# BoardA-FPGA2.net
KiCad netlist of a schematic drawn in Altium Designer
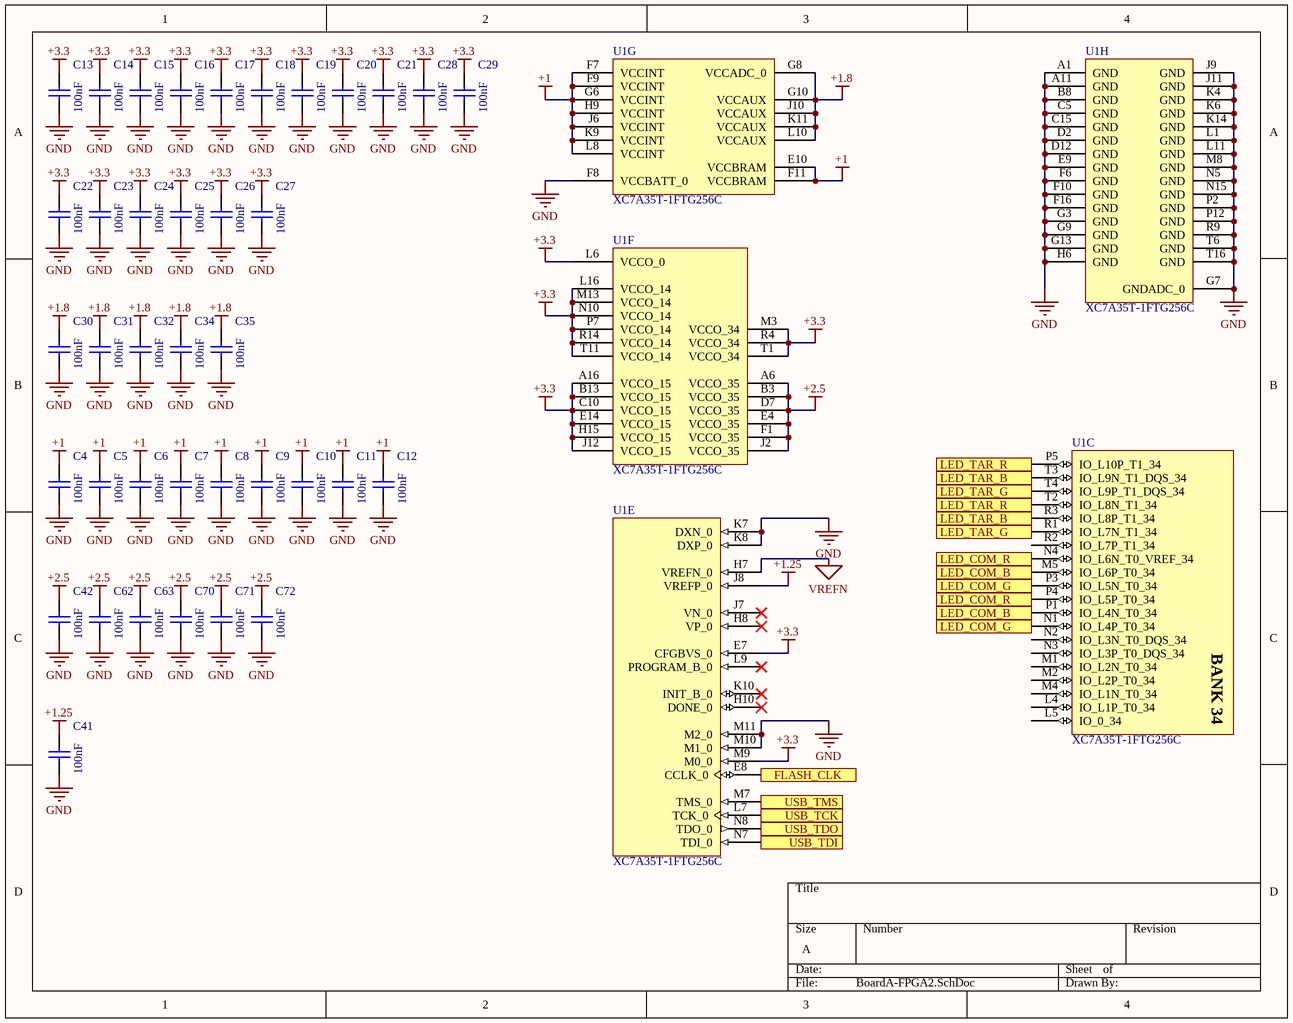
[diagram p0: BoardA-FPGA2.SchDoc]

(export (version "E")
  (design (tool "Eeschema 10.0.6"))
  (components
    (comp (ref "C4")
      (value "100nF")
      (footprint "CAPC0603X33X15ML03T05")
      (fields (field (name "MANUFACTURER") "Samsung") (field (name "PART NUMBER") "CL03A104KQ3NNNC"))
      (libsource (lib "Altium Content Vault") (part "CAP"))
    )
    (comp (ref "C5")
      (value "100nF")
      (footprint "CAPC0603X33X15ML03T05")
      (fields (field (name "MANUFACTURER") "Samsung") (field (name "PART NUMBER") "CL03A104KQ3NNNC"))
      (libsource (lib "Altium Content Vault") (part "CAP"))
    )
    (comp (ref "C6")
      (value "100nF")
      (footprint "CAPC0603X33X15ML03T05")
      (fields (field (name "MANUFACTURER") "Samsung") (field (name "PART NUMBER") "CL03A104KQ3NNNC"))
      (libsource (lib "Altium Content Vault") (part "CAP"))
    )
    (comp (ref "C7")
      (value "100nF")
      (footprint "CAPC0603X33X15ML03T05")
      (fields (field (name "MANUFACTURER") "Samsung") (field (name "PART NUMBER") "CL03A104KQ3NNNC"))
      (libsource (lib "Altium Content Vault") (part "CAP"))
    )
    (comp (ref "C8")
      (value "100nF")
      (footprint "CAPC0603X33X15ML03T05")
      (fields (field (name "MANUFACTURER") "Samsung") (field (name "PART NUMBER") "CL03A104KQ3NNNC"))
      (libsource (lib "Altium Content Vault") (part "CAP"))
    )
    (comp (ref "C9")
      (value "100nF")
      (footprint "CAPC0603X33X15ML03T05")
      (fields (field (name "MANUFACTURER") "Samsung") (field (name "PART NUMBER") "CL03A104KQ3NNNC"))
      (libsource (lib "Altium Content Vault") (part "CAP"))
    )
    (comp (ref "C10")
      (value "100nF")
      (footprint "CAPC0603X33X15ML03T05")
      (fields (field (name "MANUFACTURER") "Samsung") (field (name "PART NUMBER") "CL03A104KQ3NNNC"))
      (libsource (lib "Altium Content Vault") (part "CAP"))
    )
    (comp (ref "C11")
      (value "100nF")
      (footprint "CAPC0603X33X15ML03T05")
      (fields (field (name "MANUFACTURER") "Samsung") (field (name "PART NUMBER") "CL03A104KQ3NNNC"))
      (libsource (lib "Altium Content Vault") (part "CAP"))
    )
    (comp (ref "C12")
      (value "100nF")
      (footprint "CAPC0603X33X15ML03T05")
      (fields (field (name "MANUFACTURER") "Samsung") (field (name "PART NUMBER") "CL03A104KQ3NNNC"))
      (libsource (lib "Altium Content Vault") (part "CAP"))
    )
    (comp (ref "C13")
      (value "100nF")
      (footprint "CAPC0603X33X15ML03T05")
      (fields (field (name "MANUFACTURER") "Samsung") (field (name "PART NUMBER") "CL03A104KQ3NNNC"))
      (libsource (lib "Altium Content Vault") (part "CAP"))
    )
    (comp (ref "C14")
      (value "100nF")
      (footprint "CAPC0603X33X15ML03T05")
      (fields (field (name "MANUFACTURER") "Samsung") (field (name "PART NUMBER") "CL03A104KQ3NNNC"))
      (libsource (lib "Altium Content Vault") (part "CAP"))
    )
    (comp (ref "C15")
      (value "100nF")
      (footprint "CAPC0603X33X15ML03T05")
      (fields (field (name "MANUFACTURER") "Samsung") (field (name "PART NUMBER") "CL03A104KQ3NNNC"))
      (libsource (lib "Altium Content Vault") (part "CAP"))
    )
    (comp (ref "C16")
      (value "100nF")
      (footprint "CAPC0603X33X15ML03T05")
      (fields (field (name "MANUFACTURER") "Samsung") (field (name "PART NUMBER") "CL03A104KQ3NNNC"))
      (libsource (lib "Altium Content Vault") (part "CAP"))
    )
    (comp (ref "C17")
      (value "100nF")
      (footprint "CAPC0603X33X15ML03T05")
      (fields (field (name "MANUFACTURER") "Samsung") (field (name "PART NUMBER") "CL03A104KQ3NNNC"))
      (libsource (lib "Altium Content Vault") (part "CAP"))
    )
    (comp (ref "C18")
      (value "100nF")
      (footprint "CAPC0603X33X15ML03T05")
      (fields (field (name "MANUFACTURER") "Samsung") (field (name "PART NUMBER") "CL03A104KQ3NNNC"))
      (libsource (lib "Altium Content Vault") (part "CAP"))
    )
    (comp (ref "C19")
      (value "100nF")
      (footprint "CAPC0603X33X15ML03T05")
      (fields (field (name "MANUFACTURER") "Samsung") (field (name "PART NUMBER") "CL03A104KQ3NNNC"))
      (libsource (lib "Altium Content Vault") (part "CAP"))
    )
    (comp (ref "C20")
      (value "100nF")
      (footprint "CAPC0603X33X15ML03T05")
      (fields (field (name "MANUFACTURER") "Samsung") (field (name "PART NUMBER") "CL03A104KQ3NNNC"))
      (libsource (lib "Altium Content Vault") (part "CAP"))
    )
    (comp (ref "C21")
      (value "100nF")
      (footprint "CAPC0603X33X15ML03T05")
      (fields (field (name "MANUFACTURER") "Samsung") (field (name "PART NUMBER") "CL03A104KQ3NNNC"))
      (libsource (lib "Altium Content Vault") (part "CAP"))
    )
    (comp (ref "C22")
      (value "100nF")
      (footprint "CAPC0603X33X15ML03T05")
      (fields (field (name "MANUFACTURER") "Samsung") (field (name "PART NUMBER") "CL03A104KQ3NNNC"))
      (libsource (lib "Altium Content Vault") (part "CAP"))
    )
    (comp (ref "C23")
      (value "100nF")
      (footprint "CAPC0603X33X15ML03T05")
      (fields (field (name "MANUFACTURER") "Samsung") (field (name "PART NUMBER") "CL03A104KQ3NNNC"))
      (libsource (lib "Altium Content Vault") (part "CAP"))
    )
    (comp (ref "C24")
      (value "100nF")
      (footprint "CAPC0603X33X15ML03T05")
      (fields (field (name "MANUFACTURER") "Samsung") (field (name "PART NUMBER") "CL03A104KQ3NNNC"))
      (libsource (lib "Altium Content Vault") (part "CAP"))
    )
    (comp (ref "C25")
      (value "100nF")
      (footprint "CAPC0603X33X15ML03T05")
      (fields (field (name "MANUFACTURER") "Samsung") (field (name "PART NUMBER") "CL03A104KQ3NNNC"))
      (libsource (lib "Altium Content Vault") (part "CAP"))
    )
    (comp (ref "C26")
      (value "100nF")
      (footprint "CAPC0603X33X15ML03T05")
      (fields (field (name "MANUFACTURER") "Samsung") (field (name "PART NUMBER") "CL03A104KQ3NNNC"))
      (libsource (lib "Altium Content Vault") (part "CAP"))
    )
    (comp (ref "C27")
      (value "100nF")
      (footprint "CAPC0603X33X15ML03T05")
      (fields (field (name "MANUFACTURER") "Samsung") (field (name "PART NUMBER") "CL03A104KQ3NNNC"))
      (libsource (lib "Altium Content Vault") (part "CAP"))
    )
    (comp (ref "C28")
      (value "100nF")
      (footprint "CAPC0603X33X15ML03T05")
      (fields (field (name "MANUFACTURER") "Samsung") (field (name "PART NUMBER") "CL03A104KQ3NNNC"))
      (libsource (lib "Altium Content Vault") (part "CAP"))
    )
    (comp (ref "C29")
      (value "100nF")
      (footprint "CAPC0603X33X15ML03T05")
      (fields (field (name "MANUFACTURER") "Samsung") (field (name "PART NUMBER") "CL03A104KQ3NNNC"))
      (libsource (lib "Altium Content Vault") (part "CAP"))
    )
    (comp (ref "C30")
      (value "100nF")
      (footprint "CAPC0603X33X15ML03T05")
      (fields (field (name "MANUFACTURER") "Samsung") (field (name "PART NUMBER") "CL03A104KQ3NNNC"))
      (libsource (lib "Altium Content Vault") (part "CAP"))
    )
    (comp (ref "C31")
      (value "100nF")
      (footprint "CAPC0603X33X15ML03T05")
      (fields (field (name "MANUFACTURER") "Samsung") (field (name "PART NUMBER") "CL03A104KQ3NNNC"))
      (libsource (lib "Altium Content Vault") (part "CAP"))
    )
    (comp (ref "C32")
      (value "100nF")
      (footprint "CAPC0603X33X15ML03T05")
      (fields (field (name "MANUFACTURER") "Samsung") (field (name "PART NUMBER") "CL03A104KQ3NNNC"))
      (libsource (lib "Altium Content Vault") (part "CAP"))
    )
    (comp (ref "C34")
      (value "100nF")
      (footprint "CAPC0603X33X15ML03T05")
      (fields (field (name "MANUFACTURER") "Samsung") (field (name "PART NUMBER") "CL03A104KQ3NNNC"))
      (libsource (lib "Altium Content Vault") (part "CAP"))
    )
    (comp (ref "C35")
      (value "100nF")
      (footprint "CAPC0603X33X15ML03T05")
      (fields (field (name "MANUFACTURER") "Samsung") (field (name "PART NUMBER") "CL03A104KQ3NNNC"))
      (libsource (lib "Altium Content Vault") (part "CAP"))
    )
    (comp (ref "C41")
      (value "100nF")
      (footprint "CAPC0603X33X15ML03T05")
      (fields (field (name "MANUFACTURER") "Samsung") (field (name "PART NUMBER") "CL03A104KQ3NNNC"))
      (libsource (lib "Altium Content Vault") (part "CAP"))
    )
    (comp (ref "C42")
      (value "100nF")
      (footprint "CAPC0603X33X15ML03T05")
      (fields (field (name "MANUFACTURER") "Samsung") (field (name "PART NUMBER") "CL03A104KQ3NNNC"))
      (libsource (lib "Altium Content Vault") (part "CAP"))
    )
    (comp (ref "C62")
      (value "100nF")
      (footprint "CAPC0603X33X15ML03T05")
      (fields (field (name "MANUFACTURER") "Samsung") (field (name "PART NUMBER") "CL03A104KQ3NNNC"))
      (libsource (lib "Altium Content Vault") (part "CAP"))
    )
    (comp (ref "C63")
      (value "100nF")
      (footprint "CAPC0603X33X15ML03T05")
      (fields (field (name "MANUFACTURER") "Samsung") (field (name "PART NUMBER") "CL03A104KQ3NNNC"))
      (libsource (lib "Altium Content Vault") (part "CAP"))
    )
    (comp (ref "C70")
      (value "100nF")
      (footprint "CAPC0603X33X15ML03T05")
      (fields (field (name "MANUFACTURER") "Samsung") (field (name "PART NUMBER") "CL03A104KQ3NNNC"))
      (libsource (lib "Altium Content Vault") (part "CAP"))
    )
    (comp (ref "C71")
      (value "100nF")
      (footprint "CAPC0603X33X15ML03T05")
      (fields (field (name "MANUFACTURER") "Samsung") (field (name "PART NUMBER") "CL03A104KQ3NNNC"))
      (libsource (lib "Altium Content Vault") (part "CAP"))
    )
    (comp (ref "C72")
      (value "100nF")
      (footprint "CAPC0603X33X15ML03T05")
      (fields (field (name "MANUFACTURER") "Samsung") (field (name "PART NUMBER") "CL03A104KQ3NNNC"))
      (libsource (lib "Altium Content Vault") (part "CAP"))
    )
    (comp (ref "U1")
      (value "XC7A35T-1FTG256C")
      (footprint "FTG256")
      (description "Artix-7 FPGA, 170 User I/Os, 0 GTP, 256-Ball BGA, Speed Grade 1, Commercial Grade, Pb-Free")
      (fields (field (name "MANUFACTURER") "Xilinx"))
      (libsource (lib "") (part "XLNX-XC7A35T-FTG256_1"))
    )
  )
  (nets
    (net (code "1") (name "+1") (class "Default")
      (node (ref "C10") (pin "2") (pinfunction "2_2") (pintype "passive"))
      (node (ref "C11") (pin "2") (pinfunction "2_2") (pintype "passive"))
      (node (ref "C12") (pin "2") (pinfunction "2_2") (pintype "passive"))
      (node (ref "C4") (pin "2") (pinfunction "2_2") (pintype "passive"))
      (node (ref "C5") (pin "2") (pinfunction "2_2") (pintype "passive"))
      (node (ref "C6") (pin "2") (pinfunction "2_2") (pintype "passive"))
      (node (ref "C7") (pin "2") (pinfunction "2_2") (pintype "passive"))
      (node (ref "C8") (pin "2") (pinfunction "2_2") (pintype "passive"))
      (node (ref "C9") (pin "2") (pinfunction "2_2") (pintype "passive"))
      (node (ref "U1") (pin "E10") (pinfunction "VCCBRAM_E10") (pintype "power_in"))
      (node (ref "U1") (pin "F11") (pinfunction "VCCBRAM_F11") (pintype "power_in"))
      (node (ref "U1") (pin "F7") (pinfunction "VCCINT_F7") (pintype "power_in"))
      (node (ref "U1") (pin "F9") (pinfunction "VCCINT_F9") (pintype "power_in"))
      (node (ref "U1") (pin "G6") (pinfunction "VCCINT_G6") (pintype "power_in"))
      (node (ref "U1") (pin "H9") (pinfunction "VCCINT_H9") (pintype "power_in"))
      (node (ref "U1") (pin "J6") (pinfunction "VCCINT_J6") (pintype "power_in"))
      (node (ref "U1") (pin "K9") (pinfunction "VCCINT_K9") (pintype "power_in"))
      (node (ref "U1") (pin "L8") (pinfunction "VCCINT_L8") (pintype "power_in"))
    )
    (net (code "2") (name "+1.8") (class "Default")
      (node (ref "C30") (pin "2") (pinfunction "2_2") (pintype "passive"))
      (node (ref "C31") (pin "2") (pinfunction "2_2") (pintype "passive"))
      (node (ref "C32") (pin "2") (pinfunction "2_2") (pintype "passive"))
      (node (ref "C34") (pin "2") (pinfunction "2_2") (pintype "passive"))
      (node (ref "C35") (pin "2") (pinfunction "2_2") (pintype "passive"))
      (node (ref "U1") (pin "G10") (pinfunction "VCCAUX_G10") (pintype "power_in"))
      (node (ref "U1") (pin "G8") (pinfunction "VCCADC_0_G8") (pintype "power_in"))
      (node (ref "U1") (pin "J10") (pinfunction "VCCAUX_J10") (pintype "power_in"))
      (node (ref "U1") (pin "K11") (pinfunction "VCCAUX_K11") (pintype "power_in"))
      (node (ref "U1") (pin "L10") (pinfunction "VCCAUX_L10") (pintype "power_in"))
    )
    (net (code "3") (name "+1.25") (class "Default")
      (node (ref "C41") (pin "2") (pinfunction "2_2") (pintype "passive"))
      (node (ref "U1") (pin "J8") (pinfunction "VREFP_0_J8") (pintype "input"))
    )
    (net (code "4") (name "+2.5") (class "Default")
      (node (ref "C42") (pin "2") (pinfunction "2_2") (pintype "passive"))
      (node (ref "C62") (pin "2") (pinfunction "2_2") (pintype "passive"))
      (node (ref "C63") (pin "2") (pinfunction "2_2") (pintype "passive"))
      (node (ref "C70") (pin "2") (pinfunction "2_2") (pintype "passive"))
      (node (ref "C71") (pin "2") (pinfunction "2_2") (pintype "passive"))
      (node (ref "C72") (pin "2") (pinfunction "2_2") (pintype "passive"))
      (node (ref "U1") (pin "A6") (pinfunction "VCCO_35_A6") (pintype "power_in"))
      (node (ref "U1") (pin "B3") (pinfunction "VCCO_35_B3") (pintype "power_in"))
      (node (ref "U1") (pin "D7") (pinfunction "VCCO_35_D7") (pintype "power_in"))
      (node (ref "U1") (pin "E4") (pinfunction "VCCO_35_E4") (pintype "power_in"))
      (node (ref "U1") (pin "F1") (pinfunction "VCCO_35_F1") (pintype "power_in"))
      (node (ref "U1") (pin "J2") (pinfunction "VCCO_35_J2") (pintype "power_in"))
    )
    (net (code "5") (name "+3.3") (class "Default")
      (node (ref "C13") (pin "2") (pinfunction "2_2") (pintype "passive"))
      (node (ref "C14") (pin "2") (pinfunction "2_2") (pintype "passive"))
      (node (ref "C15") (pin "2") (pinfunction "2_2") (pintype "passive"))
      (node (ref "C16") (pin "2") (pinfunction "2_2") (pintype "passive"))
      (node (ref "C17") (pin "2") (pinfunction "2_2") (pintype "passive"))
      (node (ref "C18") (pin "2") (pinfunction "2_2") (pintype "passive"))
      (node (ref "C19") (pin "2") (pinfunction "2_2") (pintype "passive"))
      (node (ref "C20") (pin "2") (pinfunction "2_2") (pintype "passive"))
      (node (ref "C21") (pin "2") (pinfunction "2_2") (pintype "passive"))
      (node (ref "C22") (pin "2") (pinfunction "2_2") (pintype "passive"))
      (node (ref "C23") (pin "2") (pinfunction "2_2") (pintype "passive"))
      (node (ref "C24") (pin "2") (pinfunction "2_2") (pintype "passive"))
      (node (ref "C25") (pin "2") (pinfunction "2_2") (pintype "passive"))
      (node (ref "C26") (pin "2") (pinfunction "2_2") (pintype "passive"))
      (node (ref "C27") (pin "2") (pinfunction "2_2") (pintype "passive"))
      (node (ref "C28") (pin "2") (pinfunction "2_2") (pintype "passive"))
      (node (ref "C29") (pin "2") (pinfunction "2_2") (pintype "passive"))
      (node (ref "U1") (pin "A16") (pinfunction "VCCO_15_A16") (pintype "power_in"))
      (node (ref "U1") (pin "B13") (pinfunction "VCCO_15_B13") (pintype "power_in"))
      (node (ref "U1") (pin "C10") (pinfunction "VCCO_15_C10") (pintype "power_in"))
      (node (ref "U1") (pin "E14") (pinfunction "VCCO_15_E14") (pintype "power_in"))
      (node (ref "U1") (pin "E7") (pinfunction "CFGBVS_0_E7") (pintype "input"))
      (node (ref "U1") (pin "H15") (pinfunction "VCCO_15_H15") (pintype "power_in"))
      (node (ref "U1") (pin "J12") (pinfunction "VCCO_15_J12") (pintype "power_in"))
      (node (ref "U1") (pin "L16") (pinfunction "VCCO_14_L16") (pintype "power_in"))
      (node (ref "U1") (pin "L6") (pinfunction "VCCO_0_L6") (pintype "power_in"))
      (node (ref "U1") (pin "M13") (pinfunction "VCCO_14_M13") (pintype "power_in"))
      (node (ref "U1") (pin "M3") (pinfunction "VCCO_34_M3") (pintype "power_in"))
      (node (ref "U1") (pin "M9") (pinfunction "M0_0_M9") (pintype "input"))
      (node (ref "U1") (pin "N10") (pinfunction "VCCO_14_N10") (pintype "power_in"))
      (node (ref "U1") (pin "P7") (pinfunction "VCCO_14_P7") (pintype "power_in"))
      (node (ref "U1") (pin "R14") (pinfunction "VCCO_14_R14") (pintype "power_in"))
      (node (ref "U1") (pin "R4") (pinfunction "VCCO_34_R4") (pintype "power_in"))
      (node (ref "U1") (pin "T1") (pinfunction "VCCO_34_T1") (pintype "power_in"))
      (node (ref "U1") (pin "T11") (pinfunction "VCCO_14_T11") (pintype "power_in"))
    )
    (net (code "6") (name "/FLASH_CLK") (class "Default")
      (node (ref "U1") (pin "E8") (pinfunction "CCLK_0_E8") (pintype "bidirectional"))
    )
    (net (code "7") (name "/LED_COM_B") (class "Default")
      (node (ref "U1") (pin "M5") (pinfunction "IO_L6P_T0_34_M5") (pintype "bidirectional"))
      (node (ref "U1") (pin "P1") (pinfunction "IO_L4N_T0_34_P1") (pintype "bidirectional"))
    )
    (net (code "8") (name "/LED_COM_G") (class "Default")
      (node (ref "U1") (pin "N1") (pinfunction "IO_L4P_T0_34_N1") (pintype "bidirectional"))
      (node (ref "U1") (pin "P3") (pinfunction "IO_L5N_T0_34_P3") (pintype "bidirectional"))
    )
    (net (code "9") (name "/LED_COM_R") (class "Default")
      (node (ref "U1") (pin "N4") (pinfunction "IO_L6N_T0_VREF_34_N4") (pintype "bidirectional"))
      (node (ref "U1") (pin "P4") (pinfunction "IO_L5P_T0_34_P4") (pintype "bidirectional"))
    )
    (net (code "10") (name "/LED_TAR_B") (class "Default")
      (node (ref "U1") (pin "R3") (pinfunction "IO_L8P_T1_34_R3") (pintype "bidirectional"))
      (node (ref "U1") (pin "T3") (pinfunction "IO_L9N_T1_DQS_34_T3") (pintype "bidirectional"))
    )
    (net (code "11") (name "/LED_TAR_G") (class "Default")
      (node (ref "U1") (pin "R1") (pinfunction "IO_L7N_T1_34_R1") (pintype "bidirectional"))
      (node (ref "U1") (pin "T4") (pinfunction "IO_L9P_T1_DQS_34_T4") (pintype "bidirectional"))
    )
    (net (code "12") (name "/LED_TAR_R") (class "Default")
      (node (ref "U1") (pin "P5") (pinfunction "IO_L10P_T1_34_P5") (pintype "bidirectional"))
      (node (ref "U1") (pin "T2") (pinfunction "IO_L8N_T1_34_T2") (pintype "bidirectional"))
    )
    (net (code "13") (name "/USB_TCK") (class "Default")
      (node (ref "U1") (pin "L7") (pinfunction "TCK_0_L7") (pintype "input"))
    )
    (net (code "14") (name "/USB_TDI") (class "Default")
      (node (ref "U1") (pin "N7") (pinfunction "TDI_0_N7") (pintype "input"))
    )
    (net (code "15") (name "/USB_TDO") (class "Default")
      (node (ref "U1") (pin "N8") (pinfunction "TDO_0_N8") (pintype "output"))
    )
    (net (code "16") (name "/USB_TMS") (class "Default")
      (node (ref "U1") (pin "M7") (pinfunction "TMS_0_M7") (pintype "input"))
    )
    (net (code "17") (name "GND") (class "Default")
      (node (ref "C10") (pin "1") (pinfunction "1_1") (pintype "passive"))
      (node (ref "C11") (pin "1") (pinfunction "1_1") (pintype "passive"))
      (node (ref "C12") (pin "1") (pinfunction "1_1") (pintype "passive"))
      (node (ref "C13") (pin "1") (pinfunction "1_1") (pintype "passive"))
      (node (ref "C14") (pin "1") (pinfunction "1_1") (pintype "passive"))
      (node (ref "C15") (pin "1") (pinfunction "1_1") (pintype "passive"))
      (node (ref "C16") (pin "1") (pinfunction "1_1") (pintype "passive"))
      (node (ref "C17") (pin "1") (pinfunction "1_1") (pintype "passive"))
      (node (ref "C18") (pin "1") (pinfunction "1_1") (pintype "passive"))
      (node (ref "C19") (pin "1") (pinfunction "1_1") (pintype "passive"))
      (node (ref "C20") (pin "1") (pinfunction "1_1") (pintype "passive"))
      (node (ref "C21") (pin "1") (pinfunction "1_1") (pintype "passive"))
      (node (ref "C22") (pin "1") (pinfunction "1_1") (pintype "passive"))
      (node (ref "C23") (pin "1") (pinfunction "1_1") (pintype "passive"))
      (node (ref "C24") (pin "1") (pinfunction "1_1") (pintype "passive"))
      (node (ref "C25") (pin "1") (pinfunction "1_1") (pintype "passive"))
      (node (ref "C26") (pin "1") (pinfunction "1_1") (pintype "passive"))
      (node (ref "C27") (pin "1") (pinfunction "1_1") (pintype "passive"))
      (node (ref "C28") (pin "1") (pinfunction "1_1") (pintype "passive"))
      (node (ref "C29") (pin "1") (pinfunction "1_1") (pintype "passive"))
      (node (ref "C30") (pin "1") (pinfunction "1_1") (pintype "passive"))
      (node (ref "C31") (pin "1") (pinfunction "1_1") (pintype "passive"))
      (node (ref "C32") (pin "1") (pinfunction "1_1") (pintype "passive"))
      (node (ref "C34") (pin "1") (pinfunction "1_1") (pintype "passive"))
      (node (ref "C35") (pin "1") (pinfunction "1_1") (pintype "passive"))
      (node (ref "C4") (pin "1") (pinfunction "1_1") (pintype "passive"))
      (node (ref "C41") (pin "1") (pinfunction "1_1") (pintype "passive"))
      (node (ref "C42") (pin "1") (pinfunction "1_1") (pintype "passive"))
      (node (ref "C5") (pin "1") (pinfunction "1_1") (pintype "passive"))
      (node (ref "C6") (pin "1") (pinfunction "1_1") (pintype "passive"))
      (node (ref "C62") (pin "1") (pinfunction "1_1") (pintype "passive"))
      (node (ref "C63") (pin "1") (pinfunction "1_1") (pintype "passive"))
      (node (ref "C7") (pin "1") (pinfunction "1_1") (pintype "passive"))
      (node (ref "C70") (pin "1") (pinfunction "1_1") (pintype "passive"))
      (node (ref "C71") (pin "1") (pinfunction "1_1") (pintype "passive"))
      (node (ref "C72") (pin "1") (pinfunction "1_1") (pintype "passive"))
      (node (ref "C8") (pin "1") (pinfunction "1_1") (pintype "passive"))
      (node (ref "C9") (pin "1") (pinfunction "1_1") (pintype "passive"))
      (node (ref "U1") (pin "A1") (pinfunction "GND_A1") (pintype "power_in"))
      (node (ref "U1") (pin "A11") (pinfunction "GND_A11") (pintype "power_in"))
      (node (ref "U1") (pin "B8") (pinfunction "GND_B8") (pintype "power_in"))
      (node (ref "U1") (pin "C15") (pinfunction "GND_C15") (pintype "power_in"))
      (node (ref "U1") (pin "C5") (pinfunction "GND_C5") (pintype "power_in"))
      (node (ref "U1") (pin "D12") (pinfunction "GND_D12") (pintype "power_in"))
      (node (ref "U1") (pin "D2") (pinfunction "GND_D2") (pintype "power_in"))
      (node (ref "U1") (pin "E9") (pinfunction "GND_E9") (pintype "power_in"))
      (node (ref "U1") (pin "F10") (pinfunction "GND_F10") (pintype "power_in"))
      (node (ref "U1") (pin "F16") (pinfunction "GND_F16") (pintype "power_in"))
      (node (ref "U1") (pin "F6") (pinfunction "GND_F6") (pintype "power_in"))
      (node (ref "U1") (pin "F8") (pinfunction "VCCBATT_0_F8") (pintype "power_in"))
      (node (ref "U1") (pin "G13") (pinfunction "GND_G13") (pintype "power_in"))
      (node (ref "U1") (pin "G3") (pinfunction "GND_G3") (pintype "power_in"))
      (node (ref "U1") (pin "G7") (pinfunction "GNDADC_0_G7") (pintype "power_in"))
      (node (ref "U1") (pin "G9") (pinfunction "GND_G9") (pintype "power_in"))
      (node (ref "U1") (pin "H6") (pinfunction "GND_H6") (pintype "power_in"))
      (node (ref "U1") (pin "J11") (pinfunction "GND_J11") (pintype "power_in"))
      (node (ref "U1") (pin "J9") (pinfunction "GND_J9") (pintype "power_in"))
      (node (ref "U1") (pin "K14") (pinfunction "GND_K14") (pintype "power_in"))
      (node (ref "U1") (pin "K4") (pinfunction "GND_K4") (pintype "power_in"))
      (node (ref "U1") (pin "K6") (pinfunction "GND_K6") (pintype "power_in"))
      (node (ref "U1") (pin "K7") (pinfunction "DXN_0_K7") (pintype "input"))
      (node (ref "U1") (pin "K8") (pinfunction "DXP_0_K8") (pintype "input"))
      (node (ref "U1") (pin "L1") (pinfunction "GND_L1") (pintype "power_in"))
      (node (ref "U1") (pin "L11") (pinfunction "GND_L11") (pintype "power_in"))
      (node (ref "U1") (pin "M10") (pinfunction "M1_0_M10") (pintype "input"))
      (node (ref "U1") (pin "M11") (pinfunction "M2_0_M11") (pintype "input"))
      (node (ref "U1") (pin "M8") (pinfunction "GND_M8") (pintype "power_in"))
      (node (ref "U1") (pin "N15") (pinfunction "GND_N15") (pintype "power_in"))
      (node (ref "U1") (pin "N5") (pinfunction "GND_N5") (pintype "power_in"))
      (node (ref "U1") (pin "P12") (pinfunction "GND_P12") (pintype "power_in"))
      (node (ref "U1") (pin "P2") (pinfunction "GND_P2") (pintype "power_in"))
      (node (ref "U1") (pin "R9") (pinfunction "GND_R9") (pintype "power_in"))
      (node (ref "U1") (pin "T16") (pinfunction "GND_T16") (pintype "power_in"))
      (node (ref "U1") (pin "T6") (pinfunction "GND_T6") (pintype "power_in"))
    )
    (net (code "18") (name "VREFN") (class "Default")
      (node (ref "U1") (pin "H7") (pinfunction "VREFN_0_H7") (pintype "input"))
    )
    (net (code "19") (name "unconnected-(U1C-IO_0_34-PadL5)") (class "Default")
      (node (ref "U1") (pin "L5") (pinfunction "IO_0_34_L5") (pintype "bidirectional"))
    )
    (net (code "20") (name "unconnected-(U1C-IO_L1N_T0_34-PadM4)") (class "Default")
      (node (ref "U1") (pin "M4") (pinfunction "IO_L1N_T0_34_M4") (pintype "bidirectional"))
    )
    (net (code "21") (name "unconnected-(U1C-IO_L1P_T0_34-PadL4)") (class "Default")
      (node (ref "U1") (pin "L4") (pinfunction "IO_L1P_T0_34_L4") (pintype "bidirectional"))
    )
    (net (code "22") (name "unconnected-(U1C-IO_L2N_T0_34-PadM1)") (class "Default")
      (node (ref "U1") (pin "M1") (pinfunction "IO_L2N_T0_34_M1") (pintype "bidirectional"))
    )
    (net (code "23") (name "unconnected-(U1C-IO_L2P_T0_34-PadM2)") (class "Default")
      (node (ref "U1") (pin "M2") (pinfunction "IO_L2P_T0_34_M2") (pintype "bidirectional"))
    )
    (net (code "24") (name "unconnected-(U1C-IO_L3N_T0_DQS_34-PadN2)") (class "Default")
      (node (ref "U1") (pin "N2") (pinfunction "IO_L3N_T0_DQS_34_N2") (pintype "bidirectional"))
    )
    (net (code "25") (name "unconnected-(U1C-IO_L3P_T0_DQS_34-PadN3)") (class "Default")
      (node (ref "U1") (pin "N3") (pinfunction "IO_L3P_T0_DQS_34_N3") (pintype "bidirectional"))
    )
    (net (code "26") (name "unconnected-(U1C-IO_L7P_T1_34-PadR2)") (class "Default")
      (node (ref "U1") (pin "R2") (pinfunction "IO_L7P_T1_34_R2") (pintype "bidirectional"))
    )
    (net (code "27") (name "unconnected-(U1E-DONE_0-PadH10)") (class "Default")
      (node (ref "U1") (pin "H10") (pinfunction "DONE_0_H10") (pintype "bidirectional+no_connect"))
    )
    (net (code "28") (name "unconnected-(U1E-INIT_B_0-PadK10)") (class "Default")
      (node (ref "U1") (pin "K10") (pinfunction "INIT_B_0_K10") (pintype "bidirectional+no_connect"))
    )
    (net (code "29") (name "unconnected-(U1E-PROGRAM_B_0-PadL9)") (class "Default")
      (node (ref "U1") (pin "L9") (pinfunction "PROGRAM_B_0_L9") (pintype "input+no_connect"))
    )
    (net (code "30") (name "unconnected-(U1E-VN_0-PadJ7)") (class "Default")
      (node (ref "U1") (pin "J7") (pinfunction "VN_0_J7") (pintype "input+no_connect"))
    )
    (net (code "31") (name "unconnected-(U1E-VP_0-PadH8)") (class "Default")
      (node (ref "U1") (pin "H8") (pinfunction "VP_0_H8") (pintype "input+no_connect"))
    )
  )
)
